# gpiog-l.net
KiCad netlist of a schematic drawn in Altium Designer
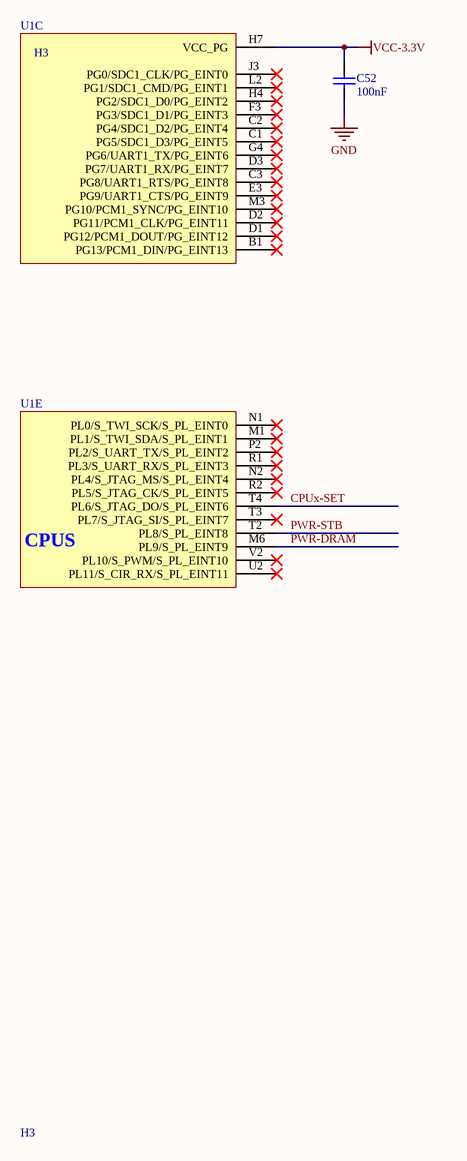
[diagram p0: gpiog-l.SchDoc]

(export (version "E")
  (design (tool "Eeschema 10.0.6"))
  (components
    (comp (ref "C52")
      (value "100nF")
      (footprint "0402_C")
      (description "smd capacitor")
      (libsource (lib "Schlib") (part "CAP-SMD"))
    )
    (comp (ref "U1")
      (value "H3")
      (footprint "allwinner-h3")
      (description "CPU")
      (libsource (lib "Schlib") (part "H3_CPU"))
    )
  )
  (nets
    (net (code "1") (name "/CPUx-SET") (class "Default")
      (node (ref "U1") (pin "T4") (pinfunction "PL6/S_JTAG_DO/S_PL_EINT6_T4") (pintype "passive"))
    )
    (net (code "2") (name "/PWR-DRAM") (class "Default")
      (node (ref "U1") (pin "M6") (pinfunction "PL9/S_PL_EINT9_M6") (pintype "passive"))
    )
    (net (code "3") (name "/PWR-STB") (class "Default")
      (node (ref "U1") (pin "T2") (pinfunction "PL8/S_PL_EINT8_T2") (pintype "passive"))
    )
    (net (code "4") (name "GND") (class "Default") (node (ref "C52") (pin "2") (pintype "passive")))
    (net (code "5") (name "VCC-3.3V") (class "Default")
      (node (ref "C52") (pin "1") (pintype "passive"))
      (node (ref "U1") (pin "H7") (pinfunction "VCC_PG_H7") (pintype "passive"))
    )
    (net (code "6") (name "unconnected-(U1C-PG0{slash}SDC1_CLK{slash}PG_EINT0-PadJ3)") (class "Default")
      (node (ref "U1") (pin "J3") (pinfunction "PG0/SDC1_CLK/PG_EINT0_J3") (pintype "passive+no_connect"))
    )
    (net (code "7") (name "unconnected-(U1C-PG1{slash}SDC1_CMD{slash}PG_EINT1-PadL2)") (class "Default")
      (node (ref "U1") (pin "L2") (pinfunction "PG1/SDC1_CMD/PG_EINT1_L2") (pintype "passive+no_connect"))
    )
    (net (code "8") (name "unconnected-(U1C-PG2{slash}SDC1_D0{slash}PG_EINT2-PadH4)") (class "Default")
      (node (ref "U1") (pin "H4") (pinfunction "PG2/SDC1_D0/PG_EINT2_H4") (pintype "passive+no_connect"))
    )
    (net (code "9") (name "unconnected-(U1C-PG3{slash}SDC1_D1{slash}PG_EINT3-PadF3)") (class "Default")
      (node (ref "U1") (pin "F3") (pinfunction "PG3/SDC1_D1/PG_EINT3_F3") (pintype "passive+no_connect"))
    )
    (net (code "10") (name "unconnected-(U1C-PG4{slash}SDC1_D2{slash}PG_EINT4-PadC2)") (class "Default")
      (node (ref "U1") (pin "C2") (pinfunction "PG4/SDC1_D2/PG_EINT4_C2") (pintype "passive+no_connect"))
    )
    (net (code "11") (name "unconnected-(U1C-PG5{slash}SDC1_D3{slash}PG_EINT5-PadC1)") (class "Default")
      (node (ref "U1") (pin "C1") (pinfunction "PG5/SDC1_D3/PG_EINT5_C1") (pintype "passive+no_connect"))
    )
    (net (code "12") (name "unconnected-(U1C-PG6{slash}UART1_TX{slash}PG_EINT6-PadG4)") (class "Default")
      (node (ref "U1") (pin "G4") (pinfunction "PG6/UART1_TX/PG_EINT6_G4") (pintype "passive+no_connect"))
    )
    (net (code "13") (name "unconnected-(U1C-PG7{slash}UART1_RX{slash}PG_EINT7-PadD3)") (class "Default")
      (node (ref "U1") (pin "D3") (pinfunction "PG7/UART1_RX/PG_EINT7_D3") (pintype "passive+no_connect"))
    )
    (net (code "14") (name "unconnected-(U1C-PG8{slash}UART1_RTS{slash}PG_EINT8-PadC3)") (class "Default")
      (node (ref "U1") (pin "C3") (pinfunction "PG8/UART1_RTS/PG_EINT8_C3") (pintype "passive+no_connect"))
    )
    (net (code "15") (name "unconnected-(U1C-PG9{slash}UART1_CTS{slash}PG_EINT9-PadE3)") (class "Default")
      (node (ref "U1") (pin "E3") (pinfunction "PG9/UART1_CTS/PG_EINT9_E3") (pintype "passive+no_connect"))
    )
    (net (code "16") (name "unconnected-(U1C-PG10{slash}PCM1_SYNC{slash}PG_EINT10-PadM3)") (class "Default")
      (node (ref "U1") (pin "M3") (pinfunction "PG10/PCM1_SYNC/PG_EINT10_M3") (pintype "passive+no_connect"))
    )
    (net (code "17") (name "unconnected-(U1C-PG11{slash}PCM1_CLK{slash}PG_EINT11-PadD2)") (class "Default")
      (node (ref "U1") (pin "D2") (pinfunction "PG11/PCM1_CLK/PG_EINT11_D2") (pintype "passive+no_connect"))
    )
    (net (code "18") (name "unconnected-(U1C-PG12{slash}PCM1_DOUT{slash}PG_EINT12-PadD1)") (class "Default")
      (node (ref "U1") (pin "D1") (pinfunction "PG12/PCM1_DOUT/PG_EINT12_D1") (pintype "passive+no_connect"))
    )
    (net (code "19") (name "unconnected-(U1C-PG13{slash}PCM1_DIN{slash}PG_EINT13-PadB1)") (class "Default")
      (node (ref "U1") (pin "B1") (pinfunction "PG13/PCM1_DIN/PG_EINT13_B1") (pintype "passive+no_connect"))
    )
    (net (code "20") (name "unconnected-(U1E-PL0{slash}S_TWI_SCK{slash}S_PL_EINT0-PadN1)") (class "Default")
      (node (ref "U1") (pin "N1") (pinfunction "PL0/S_TWI_SCK/S_PL_EINT0_N1") (pintype "passive+no_connect"))
    )
    (net (code "21") (name "unconnected-(U1E-PL1{slash}S_TWI_SDA{slash}S_PL_EINT1-PadM1)") (class "Default")
      (node (ref "U1") (pin "M1") (pinfunction "PL1/S_TWI_SDA/S_PL_EINT1_M1") (pintype "passive+no_connect"))
    )
    (net (code "22") (name "unconnected-(U1E-PL2{slash}S_UART_TX{slash}S_PL_EINT2-PadP2)") (class "Default")
      (node (ref "U1") (pin "P2") (pinfunction "PL2/S_UART_TX/S_PL_EINT2_P2") (pintype "passive+no_connect"))
    )
    (net (code "23") (name "unconnected-(U1E-PL3{slash}S_UART_RX{slash}S_PL_EINT3-PadR1)") (class "Default")
      (node (ref "U1") (pin "R1") (pinfunction "PL3/S_UART_RX/S_PL_EINT3_R1") (pintype "passive+no_connect"))
    )
    (net (code "24") (name "unconnected-(U1E-PL4{slash}S_JTAG_MS{slash}S_PL_EINT4-PadN2)") (class "Default")
      (node (ref "U1") (pin "N2") (pinfunction "PL4/S_JTAG_MS/S_PL_EINT4_N2") (pintype "passive+no_connect"))
    )
    (net (code "25") (name "unconnected-(U1E-PL5{slash}S_JTAG_CK{slash}S_PL_EINT5-PadR2)") (class "Default")
      (node (ref "U1") (pin "R2") (pinfunction "PL5/S_JTAG_CK/S_PL_EINT5_R2") (pintype "passive+no_connect"))
    )
    (net (code "26") (name "unconnected-(U1E-PL7{slash}S_JTAG_SI{slash}S_PL_EINT7-PadT3)") (class "Default")
      (node (ref "U1") (pin "T3") (pinfunction "PL7/S_JTAG_SI/S_PL_EINT7_T3") (pintype "passive+no_connect"))
    )
    (net (code "27") (name "unconnected-(U1E-PL10{slash}S_PWM{slash}S_PL_EINT10-PadV2)") (class "Default")
      (node (ref "U1") (pin "V2") (pinfunction "PL10/S_PWM/S_PL_EINT10_V2") (pintype "passive+no_connect"))
    )
    (net (code "28") (name "unconnected-(U1E-PL11{slash}S_CIR_RX{slash}S_PL_EINT11-PadU2)") (class "Default")
      (node (ref "U1") (pin "U2") (pinfunction "PL11/S_CIR_RX/S_PL_EINT11_U2") (pintype "passive+no_connect"))
    )
  )
)
